# ZeroDriftLatchComp.net
KiCad netlist of a schematic drawn in Altium Designer
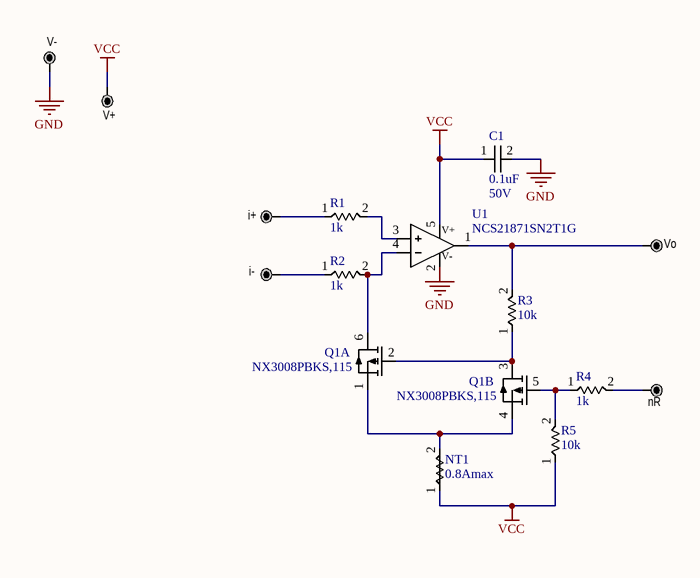
[diagram p0: ZeroDriftLatchComp.SchDoc]

(export (version "E")
  (design (tool "Eeschema 10.0.6"))
  (components
    (comp (ref "C1")
      (value "0.1uF")
      (footprint "0603 CAP")
      (description "CAP CER 0.1UF 50V X7R 0603")
      (fields
        (field (name "MFG") "Yageo")
        (field (name "MPN") "CC0603JRX7R9BB104")
        (field (name "VENDOR MAX VOLTAGE") "50V")
      )
      (libsource (lib "Schlib_SMT_Capacitors") (part "C-0603-0u10-J50V-X7RC"))
    )
    (comp (ref "i+")
      (value "Test Point PTH")
      (footprint "TP - PTH")
      (description "PTH Test Point")
      (libsource (lib "General_SchLib") (part "Test Point PTH"))
    )
    (comp (ref "i-")
      (value "Test Point PTH")
      (footprint "TP - PTH")
      (description "PTH Test Point")
      (libsource (lib "General_SchLib") (part "Test Point PTH"))
    )
    (comp (ref "nR")
      (value "Test Point PTH")
      (footprint "TP - PTH")
      (description "PTH Test Point")
      (libsource (lib "General_SchLib") (part "Test Point PTH"))
    )
    (comp (ref "NT1")
      (value "0.8Amax")
      (footprint "0603 NetTie")
      (description "RES 0 OHM 1/10W 1% 0603 SMD Thick Film Resistor")
      (libsource (lib "Schlib_SMT_Resistors") (part "0603_NetTie"))
    )
    (comp (ref "Q1")
      (value "NX3008PBKS,115")
      (footprint "SOT363")
      (description "NX3008PBKS - 30 V, 200 mA dual P-channel Trench MOSFET")
      (fields (field (name "MFG") "Nexperia"))
      (libsource (lib "General_SchLib") (part "NX3008PBKS,115"))
    )
    (comp (ref "R1")
      (value "1k")
      (footprint "0603 RES")
      (description "RES SMD 1K OHM 0.1% 1/10W 0603")
      (fields (field (name "MPN") "RT0603BRB071KL") (field (name "MFG") "Yageo"))
      (libsource (lib "Schlib_SMT_Resistors") (part "R-0603-1K00-B-G"))
    )
    (comp (ref "R2")
      (value "1k")
      (footprint "0603 RES")
      (description "RES SMD 1K OHM 0.1% 1/10W 0603")
      (fields (field (name "MPN") "RT0603BRB071KL") (field (name "MFG") "Yageo"))
      (libsource (lib "Schlib_SMT_Resistors") (part "R-0603-1K00-B-G"))
    )
    (comp (ref "R3")
      (value "10k")
      (footprint "0603 RES")
      (description "RES SMD 10K OHM 0.1% 1/10W 0603")
      (fields (field (name "MPN") "RT0603BRD0710KL") (field (name "MFG") "Yageo"))
      (libsource (lib "Schlib_SMT_Resistors") (part "R-0603-10K0-B-G"))
    )
    (comp (ref "R4")
      (value "1k")
      (footprint "0603 RES")
      (description "RES SMD 1K OHM 0.1% 1/10W 0603")
      (fields (field (name "MPN") "RT0603BRB071KL") (field (name "MFG") "Yageo"))
      (libsource (lib "Schlib_SMT_Resistors") (part "R-0603-1K00-B-G"))
    )
    (comp (ref "R5")
      (value "10k")
      (footprint "0603 RES")
      (description "RES SMD 10K OHM 0.1% 1/10W 0603")
      (fields (field (name "MPN") "RT0603BRD0710KL") (field (name "MFG") "Yageo"))
      (libsource (lib "Schlib_SMT_Resistors") (part "R-0603-10K0-B-G"))
    )
    (comp (ref "U1")
      (value "NCS21871SN2T1G")
      (footprint "SOT-23-5")
      (fields (field (name "MFG") "ON Semiconductor"))
      (libsource (lib "General_SchLib") (part "NCS21871SN2T1G"))
    )
    (comp (ref "V+")
      (value "Test Point PTH")
      (footprint "TP - PTH")
      (description "PTH Test Point")
      (libsource (lib "General_SchLib") (part "Test Point PTH"))
    )
    (comp (ref "V-")
      (value "Test Point PTH")
      (footprint "TP - PTH")
      (description "PTH Test Point")
      (libsource (lib "General_SchLib") (part "Test Point PTH"))
    )
    (comp (ref "Vo")
      (value "Test Point PTH")
      (footprint "TP - PTH")
      (description "PTH Test Point")
      (libsource (lib "General_SchLib") (part "Test Point PTH"))
    )
  )
  (nets
    (net (code "1") (name "GND") (class "Default")
      (node (ref "C1") (pin "2") (pinfunction "2_2") (pintype "passive"))
      (node (ref "U1") (pin "2") (pinfunction "Vss_2") (pintype "passive"))
      (node (ref "V-") (pin "1") (pinfunction "TP_1") (pintype "passive"))
    )
    (net (code "2") (name "Net-(Q1A-D)") (class "Default")
      (node (ref "Q1") (pin "6") (pinfunction "D_6") (pintype "passive"))
      (node (ref "R2") (pin "2") (pinfunction "2_2") (pintype "passive"))
      (node (ref "U1") (pin "4") (pinfunction "3_4") (pintype "passive"))
    )
    (net (code "3") (name "Net-(Q1A-G)") (class "Default")
      (node (ref "Q1") (pin "2") (pinfunction "G_2") (pintype "passive"))
      (node (ref "Q1") (pin "3") (pinfunction "D_3") (pintype "passive"))
      (node (ref "R3") (pin "1") (pinfunction "1_1") (pintype "passive"))
    )
    (net (code "4") (name "Net-(Q1A-S)") (class "Default")
      (node (ref "NT1") (pin "2") (pinfunction "2_2") (pintype "passive"))
      (node (ref "Q1") (pin "1") (pinfunction "S_1") (pintype "passive"))
      (node (ref "Q1") (pin "4") (pinfunction "S_4") (pintype "passive"))
    )
    (net (code "5") (name "Net-(Q1B-G)") (class "Default")
      (node (ref "Q1") (pin "5") (pinfunction "G_5") (pintype "passive"))
      (node (ref "R4") (pin "1") (pinfunction "1_1") (pintype "passive"))
      (node (ref "R5") (pin "2") (pinfunction "2_2") (pintype "passive"))
    )
    (net (code "6") (name "Net-(U1-2)") (class "Default")
      (node (ref "R1") (pin "2") (pinfunction "2_2") (pintype "passive"))
      (node (ref "U1") (pin "3") (pinfunction "2_3") (pintype "passive"))
    )
    (net (code "7") (name "Net-(Vo-TP)") (class "Default")
      (node (ref "R3") (pin "2") (pinfunction "2_2") (pintype "passive"))
      (node (ref "U1") (pin "1") (pinfunction "1_1") (pintype "passive"))
      (node (ref "Vo") (pin "1") (pinfunction "TP_1") (pintype "passive"))
    )
    (net (code "8") (name "Net-(i+-TP)") (class "Default")
      (node (ref "R1") (pin "1") (pinfunction "1_1") (pintype "passive"))
      (node (ref "i+") (pin "1") (pinfunction "TP_1") (pintype "passive"))
    )
    (net (code "9") (name "Net-(i--TP)") (class "Default")
      (node (ref "R2") (pin "1") (pinfunction "1_1") (pintype "passive"))
      (node (ref "i-") (pin "1") (pinfunction "TP_1") (pintype "passive"))
    )
    (net (code "10") (name "Net-(nR-TP)") (class "Default")
      (node (ref "R4") (pin "2") (pinfunction "2_2") (pintype "passive"))
      (node (ref "nR") (pin "1") (pinfunction "TP_1") (pintype "passive"))
    )
    (net (code "11") (name "VCC") (class "Default")
      (node (ref "C1") (pin "1") (pinfunction "1_1") (pintype "passive"))
      (node (ref "NT1") (pin "1") (pinfunction "1_1") (pintype "passive"))
      (node (ref "R5") (pin "1") (pinfunction "1_1") (pintype "passive"))
      (node (ref "U1") (pin "5") (pinfunction "Vdd_5") (pintype "passive"))
      (node (ref "V+") (pin "1") (pinfunction "TP_1") (pintype "passive"))
    )
  )
)
